# untitled-power.net
KiCad netlist of a schematic drawn in EAGLE
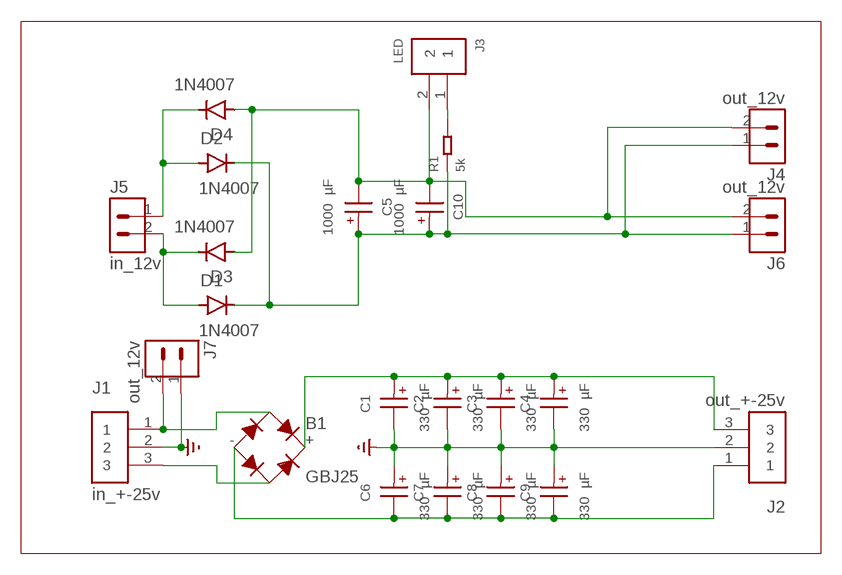
[diagram p0: schematic, sheet 1]

(export (version "E")
  (design (tool "Eeschema 10.0.6"))
  (components
    (comp (ref "B1")
      (value "GBJ25")
      (footprint "eagle-import:GBJ")
      (libsource (lib "eagle-import") (part "GBJ25"))
    )
    (comp (ref "C1")
      (value "330 µF")
      (footprint "eagle-import:WCAP-AT1H_18X35.5(DXL)")
      (libsource (lib "eagle-import") (part "WCAP-AT1H_18X35.5_860241081001"))
    )
    (comp (ref "C2")
      (value "330 µF")
      (footprint "eagle-import:WCAP-AT1H_18X35.5(DXL)")
      (libsource (lib "eagle-import") (part "WCAP-AT1H_18X35.5_860241081001"))
    )
    (comp (ref "C3")
      (value "330 µF")
      (footprint "eagle-import:WCAP-AT1H_18X35.5(DXL)")
      (libsource (lib "eagle-import") (part "WCAP-AT1H_18X35.5_860241081001"))
    )
    (comp (ref "C4")
      (value "330 µF")
      (footprint "eagle-import:WCAP-AT1H_18X35.5(DXL)")
      (libsource (lib "eagle-import") (part "WCAP-AT1H_18X35.5_860241081001"))
    )
    (comp (ref "C5")
      (value "1000 µF")
      (footprint "eagle-import:WCAP-ATET_10X25(DXL)")
      (libsource (lib "eagle-import") (part "WCAP-ATET_10X25_860130375008"))
    )
    (comp (ref "C6")
      (value "330 µF")
      (footprint "eagle-import:WCAP-AT1H_18X35.5(DXL)")
      (libsource (lib "eagle-import") (part "WCAP-AT1H_18X35.5_860241081001"))
    )
    (comp (ref "C7")
      (value "330 µF")
      (footprint "eagle-import:WCAP-AT1H_18X35.5(DXL)")
      (libsource (lib "eagle-import") (part "WCAP-AT1H_18X35.5_860241081001"))
    )
    (comp (ref "C8")
      (value "330 µF")
      (footprint "eagle-import:WCAP-AT1H_18X35.5(DXL)")
      (libsource (lib "eagle-import") (part "WCAP-AT1H_18X35.5_860241081001"))
    )
    (comp (ref "C9")
      (value "330 µF")
      (footprint "eagle-import:WCAP-AT1H_18X35.5(DXL)")
      (libsource (lib "eagle-import") (part "WCAP-AT1H_18X35.5_860241081001"))
    )
    (comp (ref "C10")
      (value "1000 µF")
      (footprint "eagle-import:WCAP-ATET_10X25(DXL)")
      (libsource (lib "eagle-import") (part "WCAP-ATET_10X25_860130375008"))
    )
    (comp (ref "D1")
      (value "1N4007")
      (footprint "eagle-import:DO-41")
      (fields
        (field (name "DIGIKEY_PART_NUMBER") "1N4007MSCT-ND")
        (field (name "MANUFACTURER") "Micro Commercial Co")
        (field (name "CREATED_BY") "PCBLayout.com")
      )
      (libsource (lib "eagle-import") (part "1N4007"))
    )
    (comp (ref "D2")
      (value "1N4007")
      (footprint "eagle-import:DO-41")
      (fields
        (field (name "DIGIKEY_PART_NUMBER") "1N4007MSCT-ND")
        (field (name "MANUFACTURER") "Micro Commercial Co")
        (field (name "CREATED_BY") "PCBLayout.com")
      )
      (libsource (lib "eagle-import") (part "1N4007"))
    )
    (comp (ref "D3")
      (value "1N4007")
      (footprint "eagle-import:DO-41")
      (fields
        (field (name "DIGIKEY_PART_NUMBER") "1N4007MSCT-ND")
        (field (name "MANUFACTURER") "Micro Commercial Co")
        (field (name "CREATED_BY") "PCBLayout.com")
      )
      (libsource (lib "eagle-import") (part "1N4007"))
    )
    (comp (ref "D4")
      (value "1N4007")
      (footprint "eagle-import:DO-41")
      (fields
        (field (name "DIGIKEY_PART_NUMBER") "1N4007MSCT-ND")
        (field (name "MANUFACTURER") "Micro Commercial Co")
        (field (name "CREATED_BY") "PCBLayout.com")
      )
      (libsource (lib "eagle-import") (part "1N4007"))
    )
    (comp (ref "J1")
      (value "in_+-25v")
      (footprint "eagle-import:TERMINALBLOCK_PLUGGABLE-3-7.62MM")
      (fields
        (field (name "DIGIKEY_PART_NO") "732-2824-ND")
        (field (name "MANUFACTURER") "WURTH ELEKTRONIK")
        (field (name "MPN") "691311400103")
        (field (name "CREATED_BY") "PCBLayout.com")
      )
      (libsource (lib "eagle-import") (part "691311400103"))
    )
    (comp (ref "J2")
      (value "out_+-25v")
      (footprint "eagle-import:TERMINALBLOCK_PLUGGABLE-3-7.62MM")
      (fields
        (field (name "DIGIKEY_PART_NO") "732-2824-ND")
        (field (name "MANUFACTURER") "WURTH ELEKTRONIK")
        (field (name "MPN") "691311400103")
        (field (name "CREATED_BY") "PCBLayout.com")
      )
      (libsource (lib "eagle-import") (part "691311400103"))
    )
    (comp (ref "J3")
      (value "LED")
      (footprint "eagle-import:61300211121")
      (fields
        (field (name "DIGI_KEY_PART_NUMBER") "732-5315-ND")
        (field (name "MANUFACTURER") "Wurth Electronics Inc.")
        (field (name "MPN") "61300211121")
        (field (name "CREATED_BY") "PCBLayout.com")
      )
      (libsource (lib "eagle-import") (part "61300211121"))
    )
    (comp (ref "J4")
      (value "out_12v")
      (footprint "eagle-import:HDR-02")
      (fields
        (field (name "DIGIKEY_PART_NUMBER") "455-1639-ND")
        (field (name "MANUFACTURER") "JST Sales America Inc.")
        (field (name "MPN") "B2P-VH(LF)(SN)")
        (field (name "CREATED_BY") "PCBLayout.com")
      )
      (libsource (lib "eagle-import") (part "B2P-VH(LF)(SN)"))
    )
    (comp (ref "J5")
      (value "in_12v")
      (footprint "eagle-import:HDR-02")
      (fields
        (field (name "DIGIKEY_PART_NUMBER") "455-1639-ND")
        (field (name "MANUFACTURER") "JST Sales America Inc.")
        (field (name "MPN") "B2P-VH(LF)(SN)")
        (field (name "CREATED_BY") "PCBLayout.com")
      )
      (libsource (lib "eagle-import") (part "B2P-VH(LF)(SN)"))
    )
    (comp (ref "J6")
      (value "out_12v")
      (footprint "eagle-import:HDR-02")
      (fields
        (field (name "DIGIKEY_PART_NUMBER") "455-1639-ND")
        (field (name "MANUFACTURER") "JST Sales America Inc.")
        (field (name "MPN") "B2P-VH(LF)(SN)")
        (field (name "CREATED_BY") "PCBLayout.com")
      )
      (libsource (lib "eagle-import") (part "B2P-VH(LF)(SN)"))
    )
    (comp (ref "J7")
      (value "out_12v")
      (footprint "eagle-import:HDR-02")
      (fields
        (field (name "DIGIKEY_PART_NUMBER") "455-1639-ND")
        (field (name "MANUFACTURER") "JST Sales America Inc.")
        (field (name "MPN") "B2P-VH(LF)(SN)")
        (field (name "CREATED_BY") "PCBLayout.com")
      )
      (libsource (lib "eagle-import") (part "B2P-VH(LF)(SN)"))
    )
    (comp (ref "R1")
      (value "5k")
      (footprint "eagle-import:PR-D2.3XL6.5MM")
      (fields (field (name "MPN") "FHCFR-1/4W-105J"))
      (libsource (lib "eagle-import") (part "DIP-RES-1M-5%-1/4W(PR-D2.3XL6.5MM)"))
    )
  )
  (nets
    (net (code "1") (name "Net-(B1-A1)") (class "Default")
      (node (ref "B1") (pin "AC1") (pinfunction "A1_AC1") (pintype "passive"))
      (node (ref "J1") (pin "1") (pinfunction "1_1") (pintype "passive"))
      (node (ref "J7") (pin "2") (pinfunction "2_2") (pintype "passive"))
    )
    (net (code "2") (name "Net-(B1-A2)") (class "Default")
      (node (ref "B1") (pin "AC2") (pinfunction "A2_AC2") (pintype "passive"))
      (node (ref "J1") (pin "3") (pinfunction "3_3") (pintype "passive"))
    )
    (net (code "3") (name "Net-(C1-+)") (class "Default")
      (node (ref "B1") (pin "+") (pinfunction "+_+") (pintype "passive"))
      (node (ref "C1") (pin "1") (pinfunction "+_1") (pintype "passive"))
      (node (ref "C2") (pin "1") (pinfunction "+_1") (pintype "passive"))
      (node (ref "C3") (pin "1") (pinfunction "+_1") (pintype "passive"))
      (node (ref "C4") (pin "1") (pinfunction "+_1") (pintype "passive"))
      (node (ref "J2") (pin "3") (pinfunction "3_3") (pintype "passive"))
    )
    (net (code "4") (name "Net-(C6--)") (class "Default")
      (node (ref "B1") (pin "-") (pinfunction "-_-") (pintype "passive"))
      (node (ref "C6") (pin "2") (pinfunction "-_2") (pintype "passive"))
      (node (ref "C7") (pin "2") (pinfunction "-_2") (pintype "passive"))
      (node (ref "C8") (pin "2") (pinfunction "-_2") (pintype "passive"))
      (node (ref "C9") (pin "2") (pinfunction "-_2") (pintype "passive"))
      (node (ref "J2") (pin "1") (pinfunction "1_1") (pintype "passive"))
    )
    (net (code "5") (name "Net-(C10-+)") (class "Default")
      (node (ref "C10") (pin "1") (pinfunction "+_1") (pintype "passive"))
      (node (ref "C5") (pin "1") (pinfunction "+_1") (pintype "passive"))
      (node (ref "D1") (pin "C") (pinfunction "C_C") (pintype "passive"))
      (node (ref "D2") (pin "C") (pinfunction "C_C") (pintype "passive"))
      (node (ref "J4") (pin "1") (pinfunction "1_1") (pintype "passive"))
      (node (ref "J6") (pin "1") (pinfunction "1_1") (pintype "passive"))
      (node (ref "R1") (pin "1") (pinfunction "1_1") (pintype "passive"))
    )
    (net (code "6") (name "Net-(C10--)") (class "Default")
      (node (ref "C10") (pin "2") (pinfunction "-_2") (pintype "passive"))
      (node (ref "C5") (pin "2") (pinfunction "-_2") (pintype "passive"))
      (node (ref "D3") (pin "A") (pinfunction "A_A") (pintype "passive"))
      (node (ref "D4") (pin "A") (pinfunction "A_A") (pintype "passive"))
      (node (ref "J3") (pin "2") (pinfunction "2_2") (pintype "passive"))
      (node (ref "J4") (pin "2") (pinfunction "2_2") (pintype "passive"))
      (node (ref "J6") (pin "2") (pinfunction "2_2") (pintype "passive"))
    )
    (net (code "7") (name "Net-(D1-PadA)") (class "Default")
      (node (ref "D1") (pin "A") (pinfunction "A_A") (pintype "passive"))
      (node (ref "D3") (pin "C") (pinfunction "C_C") (pintype "passive"))
      (node (ref "J5") (pin "2") (pinfunction "2_2") (pintype "passive"))
    )
    (net (code "8") (name "Net-(D2-PadA)") (class "Default")
      (node (ref "D2") (pin "A") (pinfunction "A_A") (pintype "passive"))
      (node (ref "D4") (pin "C") (pinfunction "C_C") (pintype "passive"))
      (node (ref "J5") (pin "1") (pinfunction "1_1") (pintype "passive"))
    )
    (net (code "9") (name "Net-(J3-Pad1)") (class "Default")
      (node (ref "J3") (pin "1") (pinfunction "1_1") (pintype "passive"))
      (node (ref "R1") (pin "2") (pinfunction "2_2") (pintype "passive"))
    )
    (net (code "10") (name "SUPPLY0_GND_") (class "Default")
      (node (ref "C1") (pin "2") (pinfunction "-_2") (pintype "passive"))
      (node (ref "C2") (pin "2") (pinfunction "-_2") (pintype "passive"))
      (node (ref "C3") (pin "2") (pinfunction "-_2") (pintype "passive"))
      (node (ref "C4") (pin "2") (pinfunction "-_2") (pintype "passive"))
      (node (ref "C6") (pin "1") (pinfunction "+_1") (pintype "passive"))
      (node (ref "C7") (pin "1") (pinfunction "+_1") (pintype "passive"))
      (node (ref "C8") (pin "1") (pinfunction "+_1") (pintype "passive"))
      (node (ref "C9") (pin "1") (pinfunction "+_1") (pintype "passive"))
      (node (ref "J1") (pin "2") (pinfunction "2_2") (pintype "passive"))
      (node (ref "J2") (pin "2") (pinfunction "2_2") (pintype "passive"))
      (node (ref "J7") (pin "1") (pinfunction "1_1") (pintype "passive"))
    )
  )
)
